# BSPD.net
KiCad netlist of a schematic drawn in Altium Designer
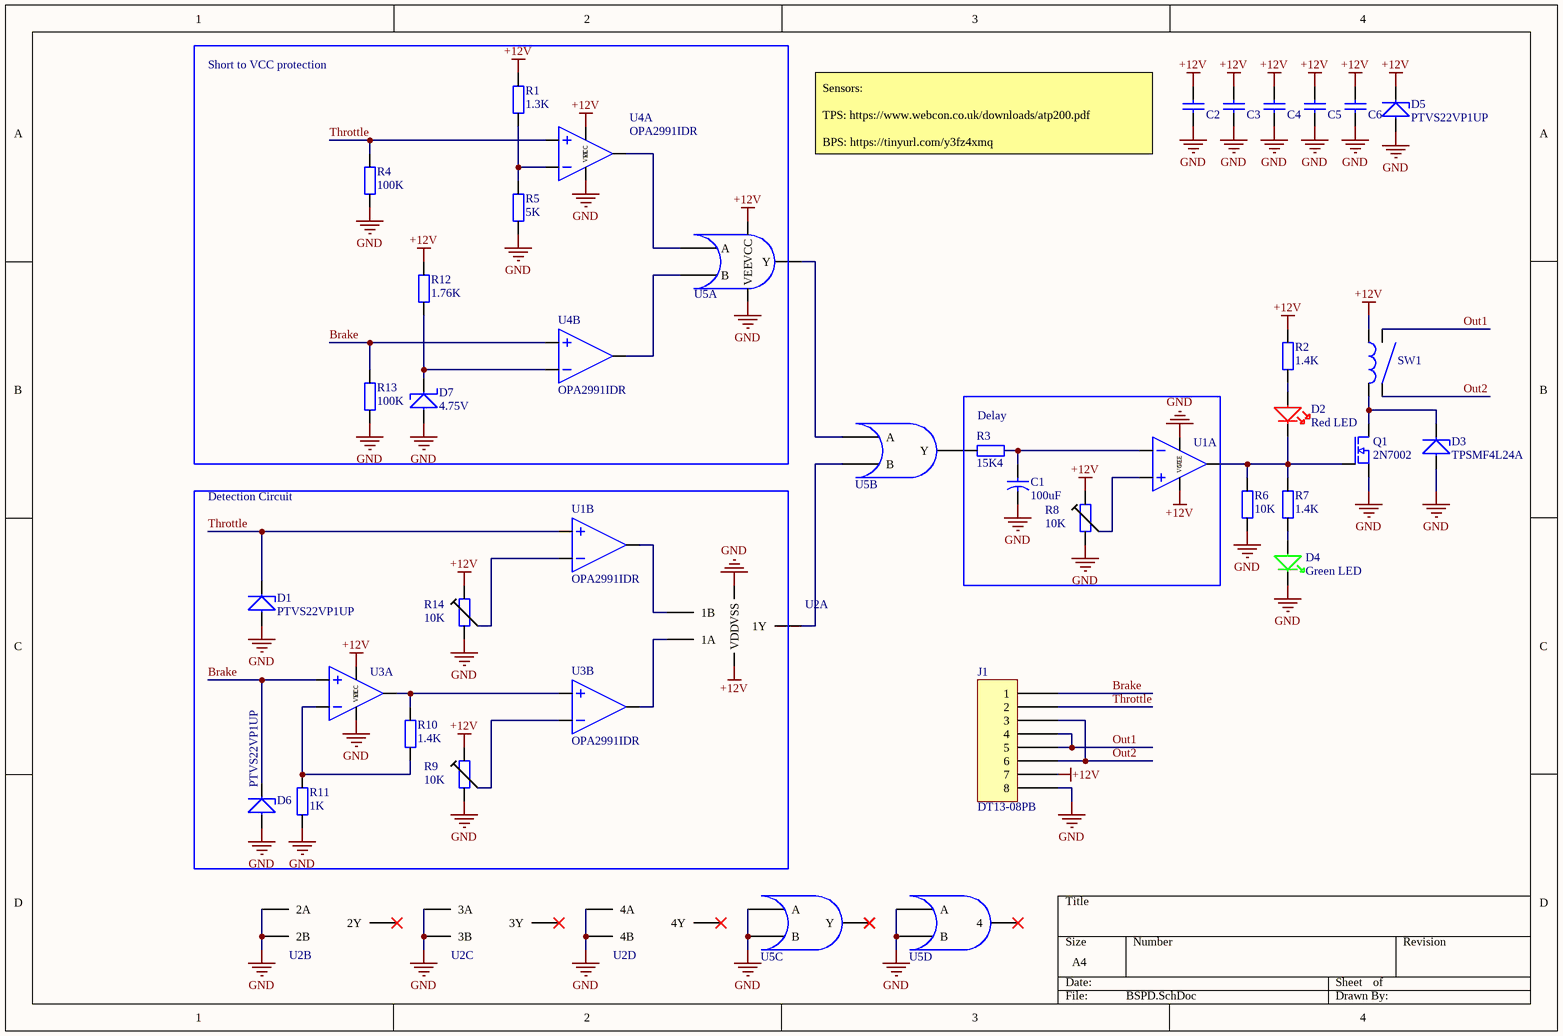
[diagram p0: BSPD.SchDoc]

(export (version "E")
  (design (tool "Eeschema 10.0.6"))
  (components
    (comp (ref "C1")
      (value "100uF")
      (footprint "CAPAE660X770D660L220X65N")
      (fields
        (field (name "PART NUMBER") "C_100uF_25V")
        (field (name "MANUFACTURER PART NUMBER") "865080445010")
      )
      (libsource (lib "FR") (part "Capacitor_P"))
    )
    (comp (ref "C2")
      (value "100nF")
      (footprint "CAPC160X80X87L35N")
      (fields
        (field (name "PART NUMBER") "C_0603_100nF_50V")
        (field (name "MANUFACTURER PART NUMBER") "CC0603MRY5V9BB104")
      )
      (libsource (lib "FR") (part "Capacitor_NP"))
    )
    (comp (ref "C3")
      (value "100nF")
      (footprint "CAPC160X80X87L35N")
      (fields
        (field (name "PART NUMBER") "C_0603_100nF_50V")
        (field (name "MANUFACTURER PART NUMBER") "CC0603MRY5V9BB104")
      )
      (libsource (lib "FR") (part "Capacitor_NP"))
    )
    (comp (ref "C4")
      (value "100nF")
      (footprint "CAPC160X80X87L35N")
      (fields
        (field (name "PART NUMBER") "C_0603_100nF_50V")
        (field (name "MANUFACTURER PART NUMBER") "CC0603MRY5V9BB104")
      )
      (libsource (lib "FR") (part "Capacitor_NP"))
    )
    (comp (ref "C5")
      (value "100nF")
      (footprint "CAPC160X80X87L35N")
      (fields
        (field (name "PART NUMBER") "C_0603_100nF_50V")
        (field (name "MANUFACTURER PART NUMBER") "CC0603MRY5V9BB104")
      )
      (libsource (lib "FR") (part "Capacitor_NP"))
    )
    (comp (ref "C6")
      (value "100nF")
      (footprint "CAPC160X80X87L35N")
      (fields
        (field (name "PART NUMBER") "C_0603_100nF_50V")
        (field (name "MANUFACTURER PART NUMBER") "CC0603MRY5V9BB104")
      )
      (libsource (lib "FR") (part "Capacitor_NP"))
    )
    (comp (ref "D1")
      (value "PTVS22VP1UP")
      (footprint "SODFL470X250X110L130X175N")
      (fields
        (field (name "PART NUMBER") "TVS_22V")
        (field (name "MANUFACTURER PART NUMBER") "PTVS22VP1UP,115")
      )
      (libsource (lib "FR") (part "TVS_Diode"))
    )
    (comp (ref "D2")
      (value "Red LED")
      (footprint "LEDC160X80X50L30N")
      (fields
        (field (name "PART NUMBER") "LED_Red_60mcd")
        (field (name "MANUFACTURER PART NUMBER") "150060SS75000")
      )
      (libsource (lib "FR") (part "LED_Red"))
    )
    (comp (ref "D3")
      (value "TPSMF4L24A")
      (footprint "SODFL470X250X110L130X175N")
      (fields (field (name "PART NUMBER") "TVS_24V"))
      (libsource (lib "FR") (part "TVS_Diode"))
    )
    (comp (ref "D4")
      (value "Green LED")
      (footprint "LEDC160X80X50L30N")
      (fields
        (field (name "PART NUMBER") "LED_Green_20mcd@12V,1.4K")
        (field (name "MANUFACTURER PART NUMBER") "150060VS55040")
      )
      (libsource (lib "FR") (part "LED_Green"))
    )
    (comp (ref "D5")
      (value "PTVS22VP1UP")
      (footprint "SODFL470X250X110L130X175N")
      (fields
        (field (name "PART NUMBER") "TVS_22V")
        (field (name "MANUFACTURER PART NUMBER") "PTVS22VP1UP,115")
      )
      (libsource (lib "FR") (part "TVS_Diode"))
    )
    (comp (ref "D6")
      (value "PTVS22VP1UP")
      (footprint "SODFL470X250X110L130X175N")
      (fields
        (field (name "PART NUMBER") "TVS_22V")
        (field (name "MANUFACTURER PART NUMBER") "PTVS22VP1UP,115")
      )
      (libsource (lib "FR") (part "TVS_Diode"))
    )
    (comp (ref "D7")
      (value "4.75V")
      (footprint "SODFL360X160X130L80X100N")
      (fields
        (field (name "PART NUMBER") "D_4.75V_625mW")
        (field (name "TOLERANCE") "2 %")
        (field (name "MANUFACTURER PART NUMBER") "PDZ4.7BGWX")
      )
      (libsource (lib "FR") (part "Zener_Diode"))
    )
    (comp (ref "J1")
      (value "DT13-08PB")
      (footprint "DT13-08PB")
      (fields (field (name "PART NUMBER") "DT13-08PB 2x4"))
      (libsource (lib "FR") (part "Connector_1x8"))
    )
    (comp (ref "Q1")
      (value "2N7002")
      (footprint "SOT23-3P95_230X110L30X43N")
      (fields (field (name "PART NUMBER") "Q_N_GSD"))
      (libsource (lib "FR") (part "Q_N_GSD"))
    )
    (comp (ref "R1")
      (value "1.3K")
      (footprint "RESC160X80X55L30N")
      (fields
        (field (name "PART NUMBER") "R_0603_1.3K_0W1_C")
        (field (name "MANUFACTURER PART NUMBER") "ERJ-3EKF1301V")
      )
      (libsource (lib "FR") (part "Resistor"))
    )
    (comp (ref "R2")
      (value "1.4K")
      (footprint "RESC160X80X50L30N")
      (fields
        (field (name "PART NUMBER") "R_0603_1.4K_0W1")
        (field (name "MANUFACTURER PART NUMBER") "RT0603DRE071K4L")
      )
      (libsource (lib "FR") (part "Resistor"))
    )
    (comp (ref "R3")
      (value "15K4")
      (footprint "RESC160X80X50L30N")
      (fields
        (field (name "PART NUMBER") "R_0603_15.4K_0W062")
        (field (name "MANUFACTURER PART NUMBER") "APC0603B15K4N")
      )
      (libsource (lib "FR") (part "Resistor"))
    )
    (comp (ref "R4")
      (value "100K")
      (footprint "RESC160X80X50L30N")
      (fields
        (field (name "PART NUMBER") "R_0603_100K_0W1_C")
        (field (name "MANUFACTURER PART NUMBER") "CRCW0603100KFKEAC")
      )
      (libsource (lib "FR") (part "Resistor"))
    )
    (comp (ref "R5")
      (value "5K")
      (footprint "RESC160X80X55L30N")
      (fields
        (field (name "PART NUMBER") "R_0603_5K_0W1_P_C")
        (field (name "MANUFACTURER PART NUMBER") "RT0603BRE075KL")
      )
      (libsource (lib "FR") (part "Resistor"))
    )
    (comp (ref "R6")
      (value "10K")
      (footprint "RESC160X80X50L30N")
      (fields
        (field (name "PART NUMBER") "R_0603_10K_0W062_P")
        (field (name "MANUFACTURER PART NUMBER") "APC0603B10K0N")
      )
      (libsource (lib "FR") (part "Resistor"))
    )
    (comp (ref "R7")
      (value "1.4K")
      (footprint "RESC160X80X50L30N")
      (fields
        (field (name "PART NUMBER") "R_0603_1.4K_0W1")
        (field (name "MANUFACTURER PART NUMBER") "RT0603DRE071K4L")
      )
      (libsource (lib "FR") (part "Resistor"))
    )
    (comp (ref "R8")
      (value "10K")
      (footprint "RESDFN3_475X200X100L160X130N")
      (fields
        (field (name "PART NUMBER") "Trimmer_10K_0W250")
        (field (name "MANUFACTURER PART NUMBER") "PVG5A103C03B00")
      )
      (libsource (lib "FR") (part "Trimmer"))
    )
    (comp (ref "R9")
      (value "10K")
      (footprint "RESDFN3_475X200X100L160X130N")
      (fields
        (field (name "PART NUMBER") "Trimmer_10K_0W250")
        (field (name "MANUFACTURER PART NUMBER") "PVG5A103C03B00")
      )
      (libsource (lib "FR") (part "Trimmer"))
    )
    (comp (ref "R10")
      (value "1.4K")
      (footprint "RESC160X80X50L30N")
      (fields
        (field (name "PART NUMBER") "R_0603_1.4K_0W1")
        (field (name "MANUFACTURER PART NUMBER") "RT0603DRE071K4L")
      )
      (libsource (lib "FR") (part "Resistor"))
    )
    (comp (ref "R11")
      (value "1K")
      (footprint "RESC160X80X50L30N")
      (fields
        (field (name "PART NUMBER") "R_0603_1K_0W1")
        (field (name "MANUFACTURER PART NUMBER") "CRCW06031K00FKEAC")
      )
      (libsource (lib "FR") (part "Resistor"))
    )
    (comp (ref "R12")
      (value "1.76K")
      (footprint "RESC160X80X50L30N")
      (fields
        (field (name "PART NUMBER") "R_0603_1.76K_0W1_P")
        (field (name "MANUFACTURER PART NUMBER") "RT0603BRD071K76L")
      )
      (libsource (lib "FR") (part "Resistor"))
    )
    (comp (ref "R13")
      (value "100K")
      (footprint "RESC160X80X50L30N")
      (fields
        (field (name "PART NUMBER") "R_0603_100K_0W1_C")
        (field (name "MANUFACTURER PART NUMBER") "CRCW0603100KFKEAC")
      )
      (libsource (lib "FR") (part "Resistor"))
    )
    (comp (ref "R14")
      (value "10K")
      (footprint "RESDFN3_475X200X100L160X130N")
      (fields
        (field (name "PART NUMBER") "Trimmer_10K_0W250")
        (field (name "MANUFACTURER PART NUMBER") "PVG5A103C03B00")
      )
      (libsource (lib "FR") (part "Trimmer"))
    )
    (comp (ref "SW1")
      (value "SPST-NO")
      (footprint "655414191282")
      (fields
        (field (name "PART NUMBER") "Relay_Non-L_TH")
        (field (name "MANUFACTURER PART NUMBER") "4-1419128-2")
      )
      (libsource (lib "FR") (part "Relay_NO"))
    )
    (comp (ref "U1")
      (value "OPA2991IDR")
      (footprint "SOIC8P127_490X599X175L84X41N")
      (libsource (lib "FR") (part "MC33202D"))
    )
    (comp (ref "U2")
      (value "HEF4081BT")
      (footprint "SOIC14P127_865X600X175L70X42N")
      (fields (field (name "MANUFACTURER PART NUMBER") "HEF4081BT,653"))
      (libsource (lib "FR") (part "HEF4081BT"))
    )
    (comp (ref "U3")
      (value "OPA2991IDR")
      (footprint "SOIC8P127_490X599X175L84X41N")
      (libsource (lib "FR") (part "MC33202D"))
    )
    (comp (ref "U4")
      (value "OPA2991IDR")
      (footprint "SOIC8P127_490X599X175L84X41N")
      (libsource (lib "FR") (part "MC33202D"))
    )
    (comp (ref "U5")
      (value "HEF4071B")
      (footprint "SOIC14P127_865X600X175L70X42N")
      (fields (field (name "MANUFACTURER PART NUMBER") "HEF4071BT,653"))
      (libsource (lib "FR") (part "HEF4071B"))
    )
  )
  (nets
    (net (code "1") (name "+12V") (class "Default")
      (node (ref "C2") (pin "1") (pinfunction "1_1") (pintype "passive"))
      (node (ref "C3") (pin "1") (pinfunction "1_1") (pintype "passive"))
      (node (ref "C4") (pin "1") (pinfunction "1_1") (pintype "passive"))
      (node (ref "C5") (pin "1") (pinfunction "1_1") (pintype "passive"))
      (node (ref "C6") (pin "1") (pinfunction "1_1") (pintype "passive"))
      (node (ref "D5") (pin "C") (pinfunction "2_C") (pintype "passive"))
      (node (ref "J1") (pin "7") (pinfunction "7_7") (pintype "passive"))
      (node (ref "R1") (pin "1") (pinfunction "1_1") (pintype "passive"))
      (node (ref "R12") (pin "1") (pinfunction "1_1") (pintype "passive"))
      (node (ref "R14") (pin "3") (pinfunction "3_3") (pintype "passive"))
      (node (ref "R2") (pin "1") (pinfunction "1_1") (pintype "passive"))
      (node (ref "R8") (pin "3") (pinfunction "3_3") (pintype "passive"))
      (node (ref "R9") (pin "3") (pinfunction "3_3") (pintype "passive"))
      (node (ref "SW1") (pin "1") (pinfunction "1_1") (pintype "passive"))
      (node (ref "U1") (pin "8") (pinfunction "VCC_8") (pintype "passive"))
      (node (ref "U2") (pin "14") (pinfunction "VDD_14") (pintype "power_in"))
      (node (ref "U3") (pin "8") (pinfunction "VCC_8") (pintype "passive"))
      (node (ref "U4") (pin "8") (pinfunction "VCC_8") (pintype "passive"))
      (node (ref "U5") (pin "14") (pinfunction "VCC_14") (pintype "passive"))
    )
    (net (code "2") (name "/Brake") (class "Default")
      (node (ref "D6") (pin "C") (pinfunction "2_C") (pintype "passive"))
      (node (ref "J1") (pin "1") (pinfunction "1_1") (pintype "passive"))
      (node (ref "R13") (pin "1") (pinfunction "1_1") (pintype "passive"))
      (node (ref "U3") (pin "3") (pinfunction "3_3") (pintype "passive"))
      (node (ref "U4") (pin "5") (pinfunction "5_5") (pintype "passive"))
    )
    (net (code "3") (name "/Out1") (class "Default")
      (node (ref "J1") (pin "4") (pinfunction "4_4") (pintype "passive"))
      (node (ref "J1") (pin "5") (pinfunction "5_5") (pintype "passive"))
      (node (ref "SW1") (pin "3") (pinfunction "3_3") (pintype "passive"))
    )
    (net (code "4") (name "/Out2") (class "Default")
      (node (ref "J1") (pin "3") (pinfunction "3_3") (pintype "passive"))
      (node (ref "J1") (pin "6") (pinfunction "6_6") (pintype "passive"))
      (node (ref "SW1") (pin "4") (pinfunction "4_4") (pintype "passive"))
    )
    (net (code "5") (name "/Throttle") (class "Default")
      (node (ref "D1") (pin "C") (pinfunction "2_C") (pintype "passive"))
      (node (ref "J1") (pin "2") (pinfunction "2_2") (pintype "passive"))
      (node (ref "R4") (pin "1") (pinfunction "1_1") (pintype "passive"))
      (node (ref "U1") (pin "5") (pinfunction "5_5") (pintype "passive"))
      (node (ref "U4") (pin "3") (pinfunction "3_3") (pintype "passive"))
    )
    (net (code "6") (name "GND") (class "Default")
      (node (ref "C1") (pin "2") (pinfunction "2_2") (pintype "passive"))
      (node (ref "C2") (pin "2") (pinfunction "2_2") (pintype "passive"))
      (node (ref "C3") (pin "2") (pinfunction "2_2") (pintype "passive"))
      (node (ref "C4") (pin "2") (pinfunction "2_2") (pintype "passive"))
      (node (ref "C5") (pin "2") (pinfunction "2_2") (pintype "passive"))
      (node (ref "C6") (pin "2") (pinfunction "2_2") (pintype "passive"))
      (node (ref "D1") (pin "A") (pinfunction "A_A") (pintype "passive"))
      (node (ref "D3") (pin "A") (pinfunction "A_A") (pintype "passive"))
      (node (ref "D4") (pin "C") (pinfunction "C_C") (pintype "passive"))
      (node (ref "D5") (pin "A") (pinfunction "A_A") (pintype "passive"))
      (node (ref "D6") (pin "A") (pinfunction "A_A") (pintype "passive"))
      (node (ref "D7") (pin "A") (pinfunction "A_A") (pintype "passive"))
      (node (ref "J1") (pin "8") (pinfunction "8_8") (pintype "passive"))
      (node (ref "Q1") (pin "2") (pinfunction "S_2") (pintype "passive"))
      (node (ref "R11") (pin "1") (pinfunction "1_1") (pintype "passive"))
      (node (ref "R13") (pin "2") (pinfunction "2_2") (pintype "passive"))
      (node (ref "R14") (pin "1") (pinfunction "1_1") (pintype "passive"))
      (node (ref "R4") (pin "2") (pinfunction "2_2") (pintype "passive"))
      (node (ref "R5") (pin "2") (pinfunction "2_2") (pintype "passive"))
      (node (ref "R6") (pin "1") (pinfunction "1_1") (pintype "passive"))
      (node (ref "R8") (pin "1") (pinfunction "1_1") (pintype "passive"))
      (node (ref "R9") (pin "1") (pinfunction "1_1") (pintype "passive"))
      (node (ref "U1") (pin "4") (pinfunction "VEE_4") (pintype "passive"))
      (node (ref "U2") (pin "12") (pinfunction "4A_12") (pintype "passive"))
      (node (ref "U2") (pin "13") (pinfunction "4B_13") (pintype "passive"))
      (node (ref "U2") (pin "5") (pinfunction "2A_5") (pintype "passive"))
      (node (ref "U2") (pin "6") (pinfunction "2B_6") (pintype "passive"))
      (node (ref "U2") (pin "7") (pinfunction "VSS_7") (pintype "passive"))
      (node (ref "U2") (pin "8") (pinfunction "3A_8") (pintype "passive"))
      (node (ref "U2") (pin "9") (pinfunction "3B_9") (pintype "passive"))
      (node (ref "U3") (pin "4") (pinfunction "VEE_4") (pintype "passive"))
      (node (ref "U4") (pin "4") (pinfunction "VEE_4") (pintype "passive"))
      (node (ref "U5") (pin "12") (pinfunction "A_12") (pintype "passive"))
      (node (ref "U5") (pin "13") (pinfunction "B_13") (pintype "passive"))
      (node (ref "U5") (pin "7") (pinfunction "VEE_7") (pintype "passive"))
      (node (ref "U5") (pin "8") (pinfunction "A_8") (pintype "passive"))
      (node (ref "U5") (pin "9") (pinfunction "B_9") (pintype "passive"))
    )
    (net (code "7") (name "Net-(C1-Pad1)") (class "Default")
      (node (ref "C1") (pin "1") (pinfunction "1_1") (pintype "passive"))
      (node (ref "R3") (pin "1") (pinfunction "1_1") (pintype "passive"))
      (node (ref "U1") (pin "2") (pinfunction "2_2") (pintype "passive"))
    )
    (net (code "8") (name "Net-(D2-PadA)") (class "Default")
      (node (ref "D2") (pin "A") (pinfunction "A_A") (pintype "passive"))
      (node (ref "R2") (pin "2") (pinfunction "2_2") (pintype "passive"))
    )
    (net (code "9") (name "Net-(D3-2)") (class "Default")
      (node (ref "D3") (pin "C") (pinfunction "2_C") (pintype "passive"))
      (node (ref "Q1") (pin "3") (pinfunction "D_3") (pintype "passive"))
      (node (ref "SW1") (pin "2") (pinfunction "2_2") (pintype "passive"))
    )
    (net (code "10") (name "Net-(D4-PadA)") (class "Default")
      (node (ref "D4") (pin "A") (pinfunction "A_A") (pintype "passive"))
      (node (ref "R7") (pin "2") (pinfunction "2_2") (pintype "passive"))
    )
    (net (code "11") (name "Net-(D7-2)") (class "Default")
      (node (ref "D7") (pin "C") (pinfunction "2_C") (pintype "passive"))
      (node (ref "R12") (pin "2") (pinfunction "2_2") (pintype "passive"))
      (node (ref "U4") (pin "6") (pinfunction "6_6") (pintype "passive"))
    )
    (net (code "12") (name "Net-(Q1-G)") (class "Default")
      (node (ref "D2") (pin "C") (pinfunction "C_C") (pintype "passive"))
      (node (ref "Q1") (pin "1") (pinfunction "G_1") (pintype "passive"))
      (node (ref "R6") (pin "2") (pinfunction "2_2") (pintype "passive"))
      (node (ref "R7") (pin "1") (pinfunction "1_1") (pintype "passive"))
      (node (ref "U1") (pin "1") (pinfunction "1_1") (pintype "passive"))
    )
    (net (code "13") (name "Net-(R1-Pad2)") (class "Default")
      (node (ref "R1") (pin "2") (pinfunction "2_2") (pintype "passive"))
      (node (ref "R5") (pin "1") (pinfunction "1_1") (pintype "passive"))
      (node (ref "U4") (pin "2") (pinfunction "2_2") (pintype "passive"))
    )
    (net (code "14") (name "Net-(R8-Pad2)") (class "Default")
      (node (ref "R8") (pin "2") (pinfunction "2_2") (pintype "passive"))
      (node (ref "U1") (pin "3") (pinfunction "3_3") (pintype "passive"))
    )
    (net (code "15") (name "Net-(R9-Pad2)") (class "Default")
      (node (ref "R9") (pin "2") (pinfunction "2_2") (pintype "passive"))
      (node (ref "U3") (pin "6") (pinfunction "6_6") (pintype "passive"))
    )
    (net (code "16") (name "Net-(R10-Pad1)") (class "Default")
      (node (ref "R10") (pin "1") (pinfunction "1_1") (pintype "passive"))
      (node (ref "R11") (pin "2") (pinfunction "2_2") (pintype "passive"))
      (node (ref "U3") (pin "2") (pinfunction "2_2") (pintype "passive"))
    )
    (net (code "17") (name "Net-(R10-Pad2)") (class "Default")
      (node (ref "R10") (pin "2") (pinfunction "2_2") (pintype "passive"))
      (node (ref "U3") (pin "1") (pinfunction "1_1") (pintype "passive"))
      (node (ref "U3") (pin "5") (pinfunction "5_5") (pintype "passive"))
    )
    (net (code "18") (name "Net-(R14-Pad2)") (class "Default")
      (node (ref "R14") (pin "2") (pinfunction "2_2") (pintype "passive"))
      (node (ref "U1") (pin "6") (pinfunction "6_6") (pintype "passive"))
    )
    (net (code "19") (name "Net-(U2A-1A)") (class "Default")
      (node (ref "U2") (pin "1") (pinfunction "1A_1") (pintype "passive"))
      (node (ref "U3") (pin "7") (pinfunction "7_7") (pintype "passive"))
    )
    (net (code "20") (name "Net-(U2A-1B)") (class "Default")
      (node (ref "U1") (pin "7") (pinfunction "7_7") (pintype "passive"))
      (node (ref "U2") (pin "2") (pinfunction "1B_2") (pintype "passive"))
    )
    (net (code "21") (name "Net-(U2A-1Y)") (class "Default")
      (node (ref "U2") (pin "3") (pinfunction "1Y_3") (pintype "passive"))
      (node (ref "U5") (pin "6") (pinfunction "B_6") (pintype "passive"))
    )
    (net (code "22") (name "Net-(U5A-A)") (class "Default")
      (node (ref "U4") (pin "1") (pinfunction "1_1") (pintype "passive"))
      (node (ref "U5") (pin "1") (pinfunction "A_1") (pintype "passive"))
    )
    (net (code "23") (name "Net-(U5A-B)") (class "Default")
      (node (ref "U4") (pin "7") (pinfunction "7_7") (pintype "passive"))
      (node (ref "U5") (pin "2") (pinfunction "B_2") (pintype "passive"))
    )
    (net (code "24") (name "Net-(U5A-Y)") (class "Default")
      (node (ref "U5") (pin "3") (pinfunction "Y_3") (pintype "passive"))
      (node (ref "U5") (pin "5") (pinfunction "A_5") (pintype "passive"))
    )
    (net (code "25") (name "Net-(U5B-Y)") (class "Default")
      (node (ref "R3") (pin "2") (pinfunction "2_2") (pintype "passive"))
      (node (ref "U5") (pin "4") (pinfunction "Y_4") (pintype "passive"))
    )
    (net (code "26") (name "unconnected-(U2B-2Y-Pad4)") (class "Default")
      (node (ref "U2") (pin "4") (pinfunction "2Y_4") (pintype "passive+no_connect"))
    )
    (net (code "27") (name "unconnected-(U2C-3Y-Pad10)") (class "Default")
      (node (ref "U2") (pin "10") (pinfunction "3Y_10") (pintype "passive+no_connect"))
    )
    (net (code "28") (name "unconnected-(U2D-4Y-Pad11)") (class "Default")
      (node (ref "U2") (pin "11") (pinfunction "4Y_11") (pintype "passive+no_connect"))
    )
    (net (code "29") (name "unconnected-(U5C-Y-Pad10)") (class "Default")
      (node (ref "U5") (pin "10") (pinfunction "Y_10") (pintype "passive+no_connect"))
    )
    (net (code "30") (name "unconnected-(U5D-4-Pad11)") (class "Default")
      (node (ref "U5") (pin "11") (pinfunction "4_11") (pintype "passive+no_connect"))
    )
  )
)
